# L293D_Motor_Driver.net
KiCad netlist of a schematic drawn in EAGLE
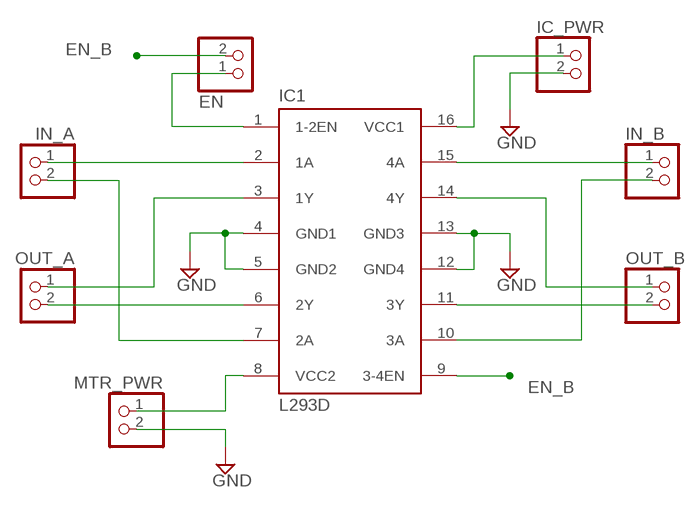
[diagram p0: schematic, sheet 1]

(export (version "E")
  (design (tool "Eeschema 10.0.6"))
  (components
    (comp (ref "EN")
      (value "PINHD-1X2")
      (footprint "eagle-import:1X02")
      (libsource (lib "eagle-import") (part "PINHD-1X2"))
    )
    (comp (ref "IC1")
      (value "L293D")
      (footprint "eagle-import:DIL16")
      (libsource (lib "eagle-import") (part "L293D"))
    )
    (comp (ref "IC_PWR")
      (value "PINHD-1X2")
      (footprint "eagle-import:1X02")
      (libsource (lib "eagle-import") (part "PINHD-1X2"))
    )
    (comp (ref "IN_A")
      (value "PINHD-1X2")
      (footprint "eagle-import:1X02")
      (libsource (lib "eagle-import") (part "PINHD-1X2"))
    )
    (comp (ref "IN_B")
      (value "PINHD-1X2")
      (footprint "eagle-import:1X02")
      (libsource (lib "eagle-import") (part "PINHD-1X2"))
    )
    (comp (ref "MTR_PWR")
      (value "PINHD-1X2")
      (footprint "eagle-import:1X02")
      (libsource (lib "eagle-import") (part "PINHD-1X2"))
    )
    (comp (ref "OUT_A")
      (value "PINHD-1X2")
      (footprint "eagle-import:1X02")
      (libsource (lib "eagle-import") (part "PINHD-1X2"))
    )
    (comp (ref "OUT_B")
      (value "PINHD-1X2")
      (footprint "eagle-import:1X02")
      (libsource (lib "eagle-import") (part "PINHD-1X2"))
    )
  )
  (nets
    (net (code "1") (name "/EN_B") (class "Default")
      (node (ref "EN") (pin "2") (pinfunction "2_2") (pintype "passive"))
      (node (ref "IC1") (pin "9") (pinfunction "3-4EN_9") (pintype "input"))
    )
    (net (code "2") (name "GND") (class "Default")
      (node (ref "IC1") (pin "12") (pinfunction "GND4_12") (pintype "power_in"))
      (node (ref "IC1") (pin "13") (pinfunction "GND3_13") (pintype "power_in"))
      (node (ref "IC1") (pin "4") (pinfunction "GND1_4") (pintype "power_in"))
      (node (ref "IC1") (pin "5") (pinfunction "GND2_5") (pintype "power_in"))
      (node (ref "IC_PWR") (pin "2") (pinfunction "2_2") (pintype "passive"))
      (node (ref "MTR_PWR") (pin "2") (pinfunction "2_2") (pintype "passive"))
    )
    (net (code "3") (name "Net-(IC1-1-2EN)") (class "Default")
      (node (ref "EN") (pin "1") (pinfunction "1_1") (pintype "passive"))
      (node (ref "IC1") (pin "1") (pinfunction "1-2EN_1") (pintype "input"))
    )
    (net (code "4") (name "Net-(IC1-1A)") (class "Default")
      (node (ref "IC1") (pin "2") (pinfunction "1A_2") (pintype "input"))
      (node (ref "IN_A") (pin "1") (pinfunction "1_1") (pintype "passive"))
    )
    (net (code "5") (name "Net-(IC1-1Y)") (class "Default")
      (node (ref "IC1") (pin "3") (pinfunction "1Y_3") (pintype "output"))
      (node (ref "OUT_A") (pin "1") (pinfunction "1_1") (pintype "passive"))
    )
    (net (code "6") (name "Net-(IC1-2A)") (class "Default")
      (node (ref "IC1") (pin "7") (pinfunction "2A_7") (pintype "input"))
      (node (ref "IN_A") (pin "2") (pinfunction "2_2") (pintype "passive"))
    )
    (net (code "7") (name "Net-(IC1-2Y)") (class "Default")
      (node (ref "IC1") (pin "6") (pinfunction "2Y_6") (pintype "output"))
      (node (ref "OUT_A") (pin "2") (pinfunction "2_2") (pintype "passive"))
    )
    (net (code "8") (name "Net-(IC1-3A)") (class "Default")
      (node (ref "IC1") (pin "10") (pinfunction "3A_10") (pintype "input"))
      (node (ref "IN_B") (pin "2") (pinfunction "2_2") (pintype "passive"))
    )
    (net (code "9") (name "Net-(IC1-3Y)") (class "Default")
      (node (ref "IC1") (pin "11") (pinfunction "3Y_11") (pintype "output"))
      (node (ref "OUT_B") (pin "2") (pinfunction "2_2") (pintype "passive"))
    )
    (net (code "10") (name "Net-(IC1-4A)") (class "Default")
      (node (ref "IC1") (pin "15") (pinfunction "4A_15") (pintype "input"))
      (node (ref "IN_B") (pin "1") (pinfunction "1_1") (pintype "passive"))
    )
    (net (code "11") (name "Net-(IC1-4Y)") (class "Default")
      (node (ref "IC1") (pin "14") (pinfunction "4Y_14") (pintype "output"))
      (node (ref "OUT_B") (pin "1") (pinfunction "1_1") (pintype "passive"))
    )
    (net (code "12") (name "Net-(IC1-VCC1)") (class "Default")
      (node (ref "IC1") (pin "16") (pinfunction "VCC1_16") (pintype "power_in"))
      (node (ref "IC_PWR") (pin "1") (pinfunction "1_1") (pintype "passive"))
    )
    (net (code "13") (name "Net-(IC1-VCC2)") (class "Default")
      (node (ref "IC1") (pin "8") (pinfunction "VCC2_8") (pintype "power_in"))
      (node (ref "MTR_PWR") (pin "1") (pinfunction "1_1") (pintype "passive"))
    )
  )
)
